# 100_MCU.net
KiCad netlist of a schematic drawn in Altium Designer
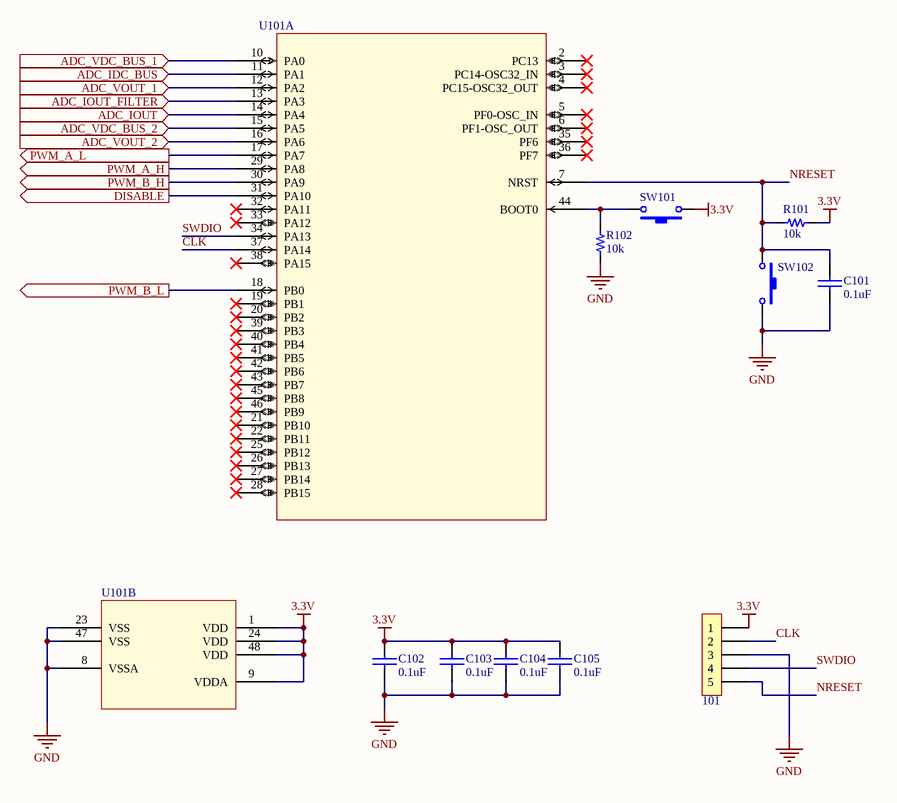
[diagram p0: 100_MCU.SchDoc]

(export (version "E")
  (design (tool "Eeschema 10.0.6"))
  (components
    (comp (ref "101")
      (value "~")
      (footprint "H_5x1_TH_100mil")
      (description "H_Male_5x1_TH_100mil")
      (libsource (lib "shared_lib_1") (part "H_Male_5x1_TH_100mil"))
    )
    (comp (ref "C101")
      (value "0.1uF")
      (footprint "0603_cap")
      (description "50V 100nF Y5V -20%~+80% 0603 Multilayer Ceramic Capacitors MLCC - SMD/SMT ROHS")
      (fields
        (field (name "MANUFACTURER") "Walsin Tech Corp")
        (field (name "MANUFACTURER PART NUMBER") "0603F104Z500CT")
      )
      (libsource (lib "shared_lib_1") (part "Cap_0.1uF_0603_50V"))
    )
    (comp (ref "C102")
      (value "0.1uF")
      (footprint "0603_cap")
      (description "CAP CER 100nF 50V Y5V 0603")
      (fields
        (field (name "MANUFACTURER") "FOJAN")
        (field (name "MANUFACTURER PART NUMBER") "FCC0603F104Z500CT")
      )
      (libsource (lib "shared_lib_1") (part "Cap_0.1uF_0603_50V"))
    )
    (comp (ref "C103")
      (value "0.1uF")
      (footprint "0603_cap")
      (description "CAP CER 100nF 50V Y5V 0603")
      (fields
        (field (name "MANUFACTURER") "FOJAN")
        (field (name "MANUFACTURER PART NUMBER") "FCC0603F104Z500CT")
      )
      (libsource (lib "shared_lib_1") (part "Cap_0.1uF_0603_50V"))
    )
    (comp (ref "C104")
      (value "0.1uF")
      (footprint "0603_cap")
      (description "CAP CER 100nF 50V Y5V 0603")
      (fields
        (field (name "MANUFACTURER") "FOJAN")
        (field (name "MANUFACTURER PART NUMBER") "FCC0603F104Z500CT")
      )
      (libsource (lib "shared_lib_1") (part "Cap_0.1uF_0603_50V"))
    )
    (comp (ref "C105")
      (value "0.1uF")
      (footprint "0603_cap")
      (description "CAP CER 100nF 50V Y5V 0603")
      (fields
        (field (name "MANUFACTURER") "FOJAN")
        (field (name "MANUFACTURER PART NUMBER") "FCC0603F104Z500CT")
      )
      (libsource (lib "shared_lib_1") (part "Cap_0.1uF_0603_50V"))
    )
    (comp (ref "R101")
      (value "10k")
      (footprint "0603_res")
      (description "RES SMD 10k OHM 5% 1/10W 0603")
      (fields (field (name "MANUFACTURER") "FOJAN") (field (name "MANUFACTURER PART NUMBER") "FRC0603J103TS"))
      (libsource (lib "shared_lib_1") (part "Res_10k_0603_1/10W"))
    )
    (comp (ref "R102")
      (value "10k")
      (footprint "0603_res")
      (description "RES SMD 10k OHM 5% 1/10W 0603")
      (fields (field (name "MANUFACTURER") "FOJAN") (field (name "MANUFACTURER PART NUMBER") "FRC0603J103TS"))
      (libsource (lib "shared_lib_1") (part "Res_10k_0603_1/10W"))
    )
    (comp (ref "SW101")
      (value "~")
      (footprint "Sw_PUSH_4.5x4.5x5mm")
      (description "SWITCH TACTILE SPST-NO 0.05A 12V")
      (fields
        (field (name "MANUFACTURER") "BZCN")
        (field (name "MANUFACTURER PART NUMBER") "TSC015A05026A")
        (field (name "LAST MODIFIED BY") "N-A.Potosi")
      )
      (libsource (lib "shared_lib_1") (part "Sw_PUSH_4.5x4.5x5.0xmm"))
    )
    (comp (ref "SW102")
      (value "~")
      (footprint "Sw_PUSH_4.5x4.5x5mm")
      (description "SWITCH TACTILE SPST-NO 0.05A 12V")
      (fields
        (field (name "MANUFACTURER") "BZCN")
        (field (name "MANUFACTURER PART NUMBER") "TSC015A05026A")
        (field (name "LAST MODIFIED BY") "N-A.Potosi")
      )
      (libsource (lib "shared_lib_1") (part "Sw_PUSH_4.5x4.5x5.0xmm"))
    )
    (comp (ref "U101")
      (value "~")
      (footprint "LQFP48_7x7mm")
      (description "IC MCU 32BIT 64KB FLASH 48LQFP")
      (fields
        (field (name "MANUFACTURER") "STMicroelectronics")
        (field (name "MANUFACTURER PART NUMBER") "STM32F030C8T6TR")
      )
      (libsource (lib "shared_lib_1") (part "IC_STM32F030C8T6TR_LQFP48_7x7MM"))
    )
  )
  (nets
    (net (code "1") (name "/ADC_IDC_BUS") (class "Default")
      (node (ref "U101") (pin "11") (pinfunction "PA1_11") (pintype "passive"))
    )
    (net (code "2") (name "/ADC_IOUT") (class "Default")
      (node (ref "U101") (pin "14") (pinfunction "PA4_14") (pintype "passive"))
    )
    (net (code "3") (name "/ADC_IOUT_FILTER") (class "Default")
      (node (ref "U101") (pin "13") (pinfunction "PA3_13") (pintype "passive"))
    )
    (net (code "4") (name "/ADC_VDC_BUS_1") (class "Default")
      (node (ref "U101") (pin "10") (pinfunction "PA0_10") (pintype "input"))
    )
    (net (code "5") (name "/ADC_VDC_BUS_2") (class "Default")
      (node (ref "U101") (pin "15") (pinfunction "PA5_15") (pintype "passive"))
    )
    (net (code "6") (name "/ADC_VOUT_1") (class "Default")
      (node (ref "U101") (pin "12") (pinfunction "PA2_12") (pintype "passive"))
    )
    (net (code "7") (name "/ADC_VOUT_2") (class "Default")
      (node (ref "U101") (pin "16") (pinfunction "PA6_16") (pintype "passive"))
    )
    (net (code "8") (name "/CLK") (class "Default")
      (node (ref "101") (pin "2") (pinfunction "2_2") (pintype "passive"))
      (node (ref "U101") (pin "37") (pinfunction "PA14_37") (pintype "passive"))
    )
    (net (code "9") (name "/DISABLE") (class "Default")
      (node (ref "U101") (pin "31") (pinfunction "PA10_31") (pintype "passive"))
    )
    (net (code "10") (name "/NRESET") (class "Default")
      (node (ref "101") (pin "5") (pinfunction "5_5") (pintype "passive"))
      (node (ref "C101") (pin "1") (pinfunction "1_1") (pintype "passive"))
      (node (ref "R101") (pin "1") (pinfunction "1_1") (pintype "passive"))
      (node (ref "SW102") (pin "1") (pinfunction "1_1") (pintype "passive"))
      (node (ref "U101") (pin "7") (pinfunction "NRST_7") (pintype "passive"))
    )
    (net (code "11") (name "/PWM_A_H") (class "Default")
      (node (ref "U101") (pin "29") (pinfunction "PA8_29") (pintype "passive"))
    )
    (net (code "12") (name "/PWM_A_L") (class "Default")
      (node (ref "U101") (pin "17") (pinfunction "PA7_17") (pintype "passive"))
    )
    (net (code "13") (name "/PWM_B_H") (class "Default")
      (node (ref "U101") (pin "30") (pinfunction "PA9_30") (pintype "passive"))
    )
    (net (code "14") (name "/PWM_B_L") (class "Default")
      (node (ref "U101") (pin "18") (pinfunction "PB0_18") (pintype "passive"))
    )
    (net (code "15") (name "/SWDIO") (class "Default")
      (node (ref "101") (pin "4") (pinfunction "4_4") (pintype "passive"))
      (node (ref "U101") (pin "34") (pinfunction "PA13_34") (pintype "passive"))
    )
    (net (code "16") (name "3.3V") (class "Default")
      (node (ref "101") (pin "1") (pinfunction "1_1") (pintype "passive"))
      (node (ref "C102") (pin "1") (pinfunction "1_1") (pintype "passive"))
      (node (ref "C103") (pin "1") (pinfunction "1_1") (pintype "passive"))
      (node (ref "C104") (pin "1") (pinfunction "1_1") (pintype "passive"))
      (node (ref "C105") (pin "1") (pinfunction "1_1") (pintype "passive"))
      (node (ref "R101") (pin "2") (pinfunction "2_2") (pintype "passive"))
      (node (ref "SW101") (pin "1") (pinfunction "1_1") (pintype "passive"))
      (node (ref "U101") (pin "1") (pinfunction "VDD_1") (pintype "power_in"))
      (node (ref "U101") (pin "24") (pinfunction "VDD_24") (pintype "power_in"))
      (node (ref "U101") (pin "48") (pinfunction "VDD_48") (pintype "power_in"))
      (node (ref "U101") (pin "9") (pinfunction "VDDA_9") (pintype "power_in"))
    )
    (net (code "17") (name "GND") (class "Default")
      (node (ref "101") (pin "3") (pinfunction "3_3") (pintype "passive"))
      (node (ref "C101") (pin "2") (pinfunction "2_2") (pintype "passive"))
      (node (ref "C102") (pin "2") (pinfunction "2_2") (pintype "passive"))
      (node (ref "C103") (pin "2") (pinfunction "2_2") (pintype "passive"))
      (node (ref "C104") (pin "2") (pinfunction "2_2") (pintype "passive"))
      (node (ref "C105") (pin "2") (pinfunction "2_2") (pintype "passive"))
      (node (ref "R102") (pin "1") (pinfunction "1_1") (pintype "passive"))
      (node (ref "SW102") (pin "2") (pinfunction "2_2") (pintype "passive"))
      (node (ref "U101") (pin "23") (pinfunction "VSS_23") (pintype "power_in"))
      (node (ref "U101") (pin "47") (pinfunction "VSS_47") (pintype "power_in"))
      (node (ref "U101") (pin "8") (pinfunction "VSSA_8") (pintype "power_in"))
    )
    (net (code "18") (name "Net-(U101A-BOOT0)") (class "Default")
      (node (ref "R102") (pin "2") (pinfunction "2_2") (pintype "passive"))
      (node (ref "SW101") (pin "2") (pinfunction "2_2") (pintype "passive"))
      (node (ref "U101") (pin "44") (pinfunction "BOOT0_44") (pintype "passive"))
    )
    (net (code "19") (name "unconnected-(U101A-PA11-Pad32)") (class "Default")
      (node (ref "U101") (pin "32") (pinfunction "PA11_32") (pintype "passive+no_connect"))
    )
    (net (code "20") (name "unconnected-(U101A-PA12-Pad33)") (class "Default")
      (node (ref "U101") (pin "33") (pinfunction "PA12_33") (pintype "bidirectional+no_connect"))
    )
    (net (code "21") (name "unconnected-(U101A-PA15-Pad38)") (class "Default")
      (node (ref "U101") (pin "38") (pinfunction "PA15_38") (pintype "bidirectional+no_connect"))
    )
    (net (code "22") (name "unconnected-(U101A-PB1-Pad19)") (class "Default")
      (node (ref "U101") (pin "19") (pinfunction "PB1_19") (pintype "bidirectional+no_connect"))
    )
    (net (code "23") (name "unconnected-(U101A-PB2-Pad20)") (class "Default")
      (node (ref "U101") (pin "20") (pinfunction "PB2_20") (pintype "bidirectional+no_connect"))
    )
    (net (code "24") (name "unconnected-(U101A-PB3-Pad39)") (class "Default")
      (node (ref "U101") (pin "39") (pinfunction "PB3_39") (pintype "bidirectional+no_connect"))
    )
    (net (code "25") (name "unconnected-(U101A-PB4-Pad40)") (class "Default")
      (node (ref "U101") (pin "40") (pinfunction "PB4_40") (pintype "bidirectional+no_connect"))
    )
    (net (code "26") (name "unconnected-(U101A-PB5-Pad41)") (class "Default")
      (node (ref "U101") (pin "41") (pinfunction "PB5_41") (pintype "bidirectional+no_connect"))
    )
    (net (code "27") (name "unconnected-(U101A-PB6-Pad42)") (class "Default")
      (node (ref "U101") (pin "42") (pinfunction "PB6_42") (pintype "bidirectional+no_connect"))
    )
    (net (code "28") (name "unconnected-(U101A-PB7-Pad43)") (class "Default")
      (node (ref "U101") (pin "43") (pinfunction "PB7_43") (pintype "bidirectional+no_connect"))
    )
    (net (code "29") (name "unconnected-(U101A-PB8-Pad45)") (class "Default")
      (node (ref "U101") (pin "45") (pinfunction "PB8_45") (pintype "bidirectional+no_connect"))
    )
    (net (code "30") (name "unconnected-(U101A-PB9-Pad46)") (class "Default")
      (node (ref "U101") (pin "46") (pinfunction "PB9_46") (pintype "bidirectional+no_connect"))
    )
    (net (code "31") (name "unconnected-(U101A-PB10-Pad21)") (class "Default")
      (node (ref "U101") (pin "21") (pinfunction "PB10_21") (pintype "bidirectional+no_connect"))
    )
    (net (code "32") (name "unconnected-(U101A-PB11-Pad22)") (class "Default")
      (node (ref "U101") (pin "22") (pinfunction "PB11_22") (pintype "bidirectional+no_connect"))
    )
    (net (code "33") (name "unconnected-(U101A-PB12-Pad25)") (class "Default")
      (node (ref "U101") (pin "25") (pinfunction "PB12_25") (pintype "bidirectional+no_connect"))
    )
    (net (code "34") (name "unconnected-(U101A-PB13-Pad26)") (class "Default")
      (node (ref "U101") (pin "26") (pinfunction "PB13_26") (pintype "bidirectional+no_connect"))
    )
    (net (code "35") (name "unconnected-(U101A-PB14-Pad27)") (class "Default")
      (node (ref "U101") (pin "27") (pinfunction "PB14_27") (pintype "bidirectional+no_connect"))
    )
    (net (code "36") (name "unconnected-(U101A-PB15-Pad28)") (class "Default")
      (node (ref "U101") (pin "28") (pinfunction "PB15_28") (pintype "bidirectional+no_connect"))
    )
    (net (code "37") (name "unconnected-(U101A-PC13-Pad2)") (class "Default")
      (node (ref "U101") (pin "2") (pinfunction "PC13_2") (pintype "bidirectional+no_connect"))
    )
    (net (code "38") (name "unconnected-(U101A-PC14-OSC32_IN-Pad3)") (class "Default")
      (node (ref "U101") (pin "3") (pinfunction "PC14-OSC32_IN_3") (pintype "bidirectional+no_connect"))
    )
    (net (code "39") (name "unconnected-(U101A-PC15-OSC32_OUT-Pad4)") (class "Default")
      (node (ref "U101") (pin "4") (pinfunction "PC15-OSC32_OUT_4") (pintype "bidirectional+no_connect"))
    )
    (net (code "40") (name "unconnected-(U101A-PF0-OSC_IN-Pad5)") (class "Default")
      (node (ref "U101") (pin "5") (pinfunction "PF0-OSC_IN_5") (pintype "bidirectional+no_connect"))
    )
    (net (code "41") (name "unconnected-(U101A-PF1-OSC_OUT-Pad6)") (class "Default")
      (node (ref "U101") (pin "6") (pinfunction "PF1-OSC_OUT_6") (pintype "bidirectional+no_connect"))
    )
    (net (code "42") (name "unconnected-(U101A-PF6-Pad35)") (class "Default")
      (node (ref "U101") (pin "35") (pinfunction "PF6_35") (pintype "bidirectional+no_connect"))
    )
    (net (code "43") (name "unconnected-(U101A-PF7-Pad36)") (class "Default")
      (node (ref "U101") (pin "36") (pinfunction "PF7_36") (pintype "bidirectional+no_connect"))
    )
  )
)
